# SECAM-TDA.net
KiCad netlist of a schematic drawn in EAGLE
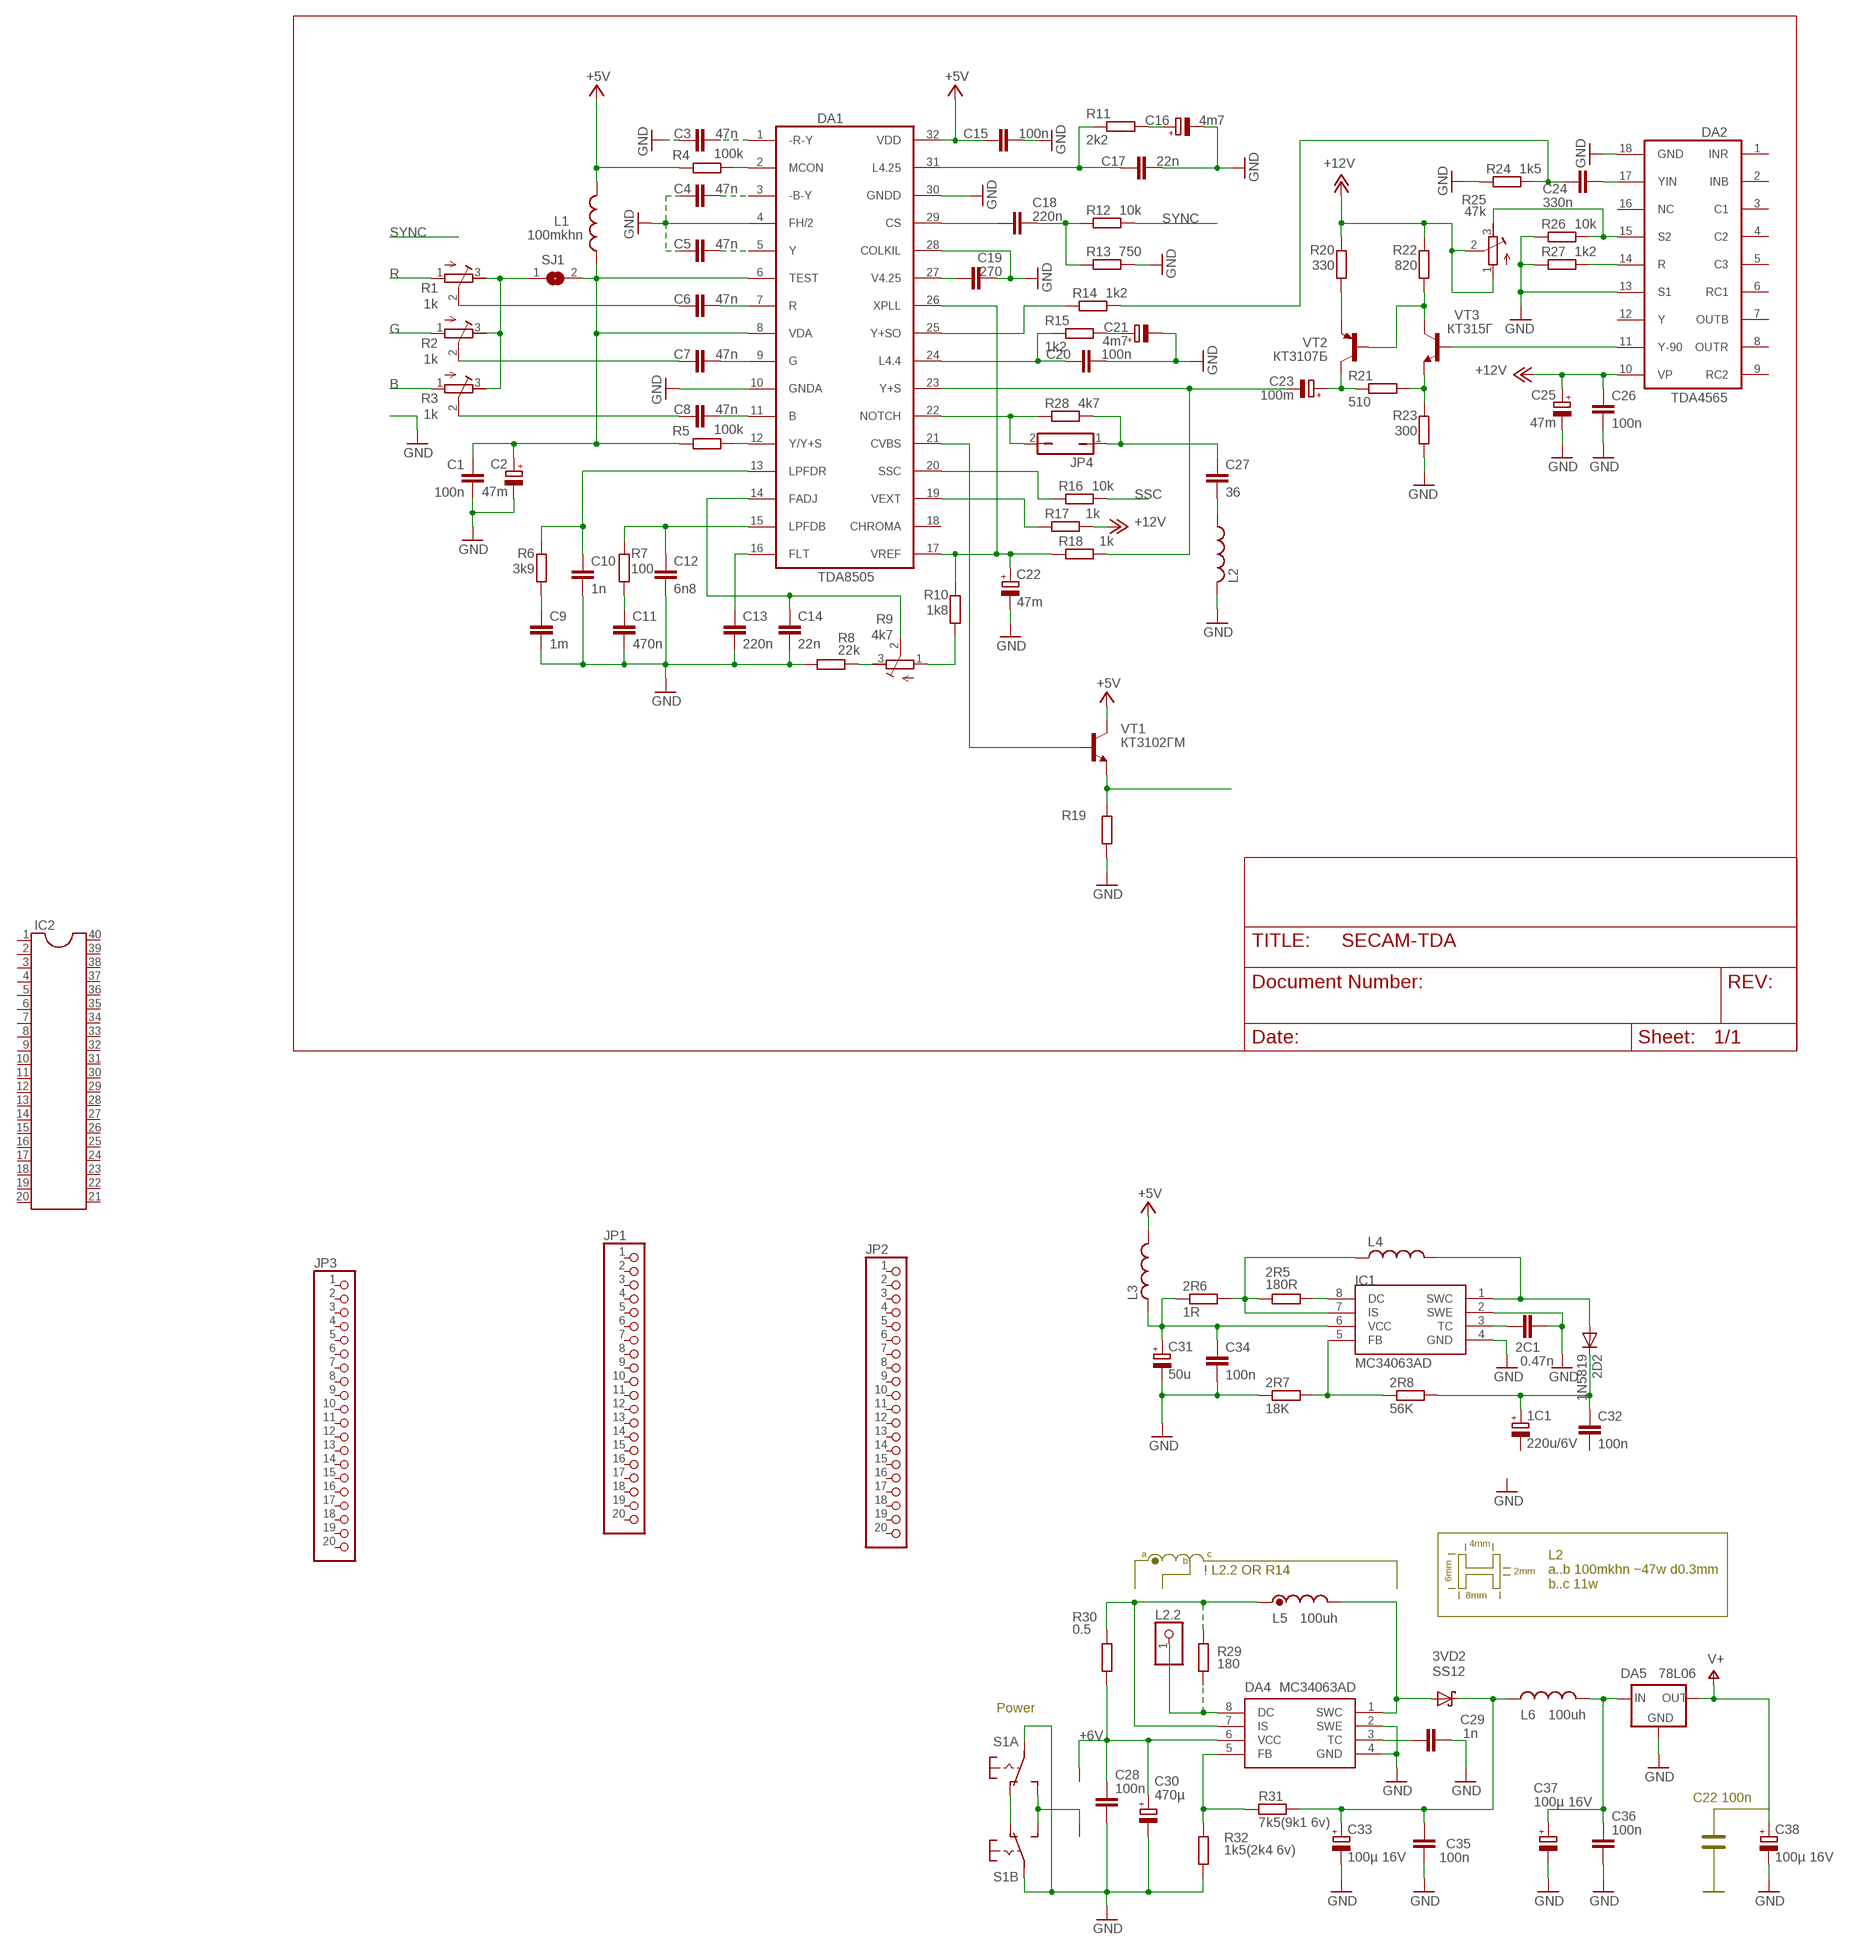
[diagram p0: schematic, sheet 1]

(export (version "E")
  (design (tool "Eeschema 10.0.6"))
  (components
    (comp (ref "1C1")
      (value "220u/6V")
      (footprint "eagle-import:E3,5-8")
      (libsource (lib "eagle-import") (part "resistor_CPOL-EUE3.5-8"))
    )
    (comp (ref "2C1")
      (value "0.47n")
      (footprint "eagle-import:C0805K")
      (libsource (lib "eagle-import") (part "resistor_C-EUC0805K"))
    )
    (comp (ref "2D2")
      (value "1N5819")
      (footprint "eagle-import:SMB")
      (libsource (lib "eagle-import") (part "DIODE-SMB"))
    )
    (comp (ref "2R5")
      (value "180R")
      (footprint "eagle-import:R0805")
      (libsource (lib "eagle-import") (part "resistor_R-EU_R0805"))
    )
    (comp (ref "2R6")
      (value "1R")
      (footprint "eagle-import:R0805")
      (libsource (lib "eagle-import") (part "resistor_R-EU_R0805"))
    )
    (comp (ref "2R7")
      (value "18K")
      (footprint "eagle-import:R0805")
      (libsource (lib "eagle-import") (part "resistor_R-EU_R0805"))
    )
    (comp (ref "2R8")
      (value "56K")
      (footprint "eagle-import:R0805")
      (libsource (lib "eagle-import") (part "resistor_R-EU_R0805"))
    )
    (comp (ref "3VD2")
      (value "SS12")
      (footprint "eagle-import:SMB")
      (libsource (lib "eagle-import") (part "SCHOTTKY-DIODESMD"))
    )
    (comp (ref "C1")
      (value "100n")
      (footprint "eagle-import:C0805")
      (libsource (lib "eagle-import") (part "rcl_C-EUC0805"))
    )
    (comp (ref "C2")
      (value "47m")
      (footprint "eagle-import:E2,5-5")
      (libsource (lib "eagle-import") (part "CPOL-EUE2.5-5"))
    )
    (comp (ref "C3")
      (value "47n")
      (footprint "eagle-import:C025-025X050")
      (libsource (lib "eagle-import") (part "rcl_C-EU025-025X050"))
    )
    (comp (ref "C4")
      (value "47n")
      (footprint "eagle-import:C025-025X050")
      (libsource (lib "eagle-import") (part "rcl_C-EU025-025X050"))
    )
    (comp (ref "C5")
      (value "47n")
      (footprint "eagle-import:C025-025X050")
      (libsource (lib "eagle-import") (part "rcl_C-EU025-025X050"))
    )
    (comp (ref "C6")
      (value "47n")
      (footprint "eagle-import:C025-025X050")
      (libsource (lib "eagle-import") (part "rcl_C-EU025-025X050"))
    )
    (comp (ref "C7")
      (value "47n")
      (footprint "eagle-import:C025-025X050")
      (libsource (lib "eagle-import") (part "rcl_C-EU025-025X050"))
    )
    (comp (ref "C8")
      (value "47n")
      (footprint "eagle-import:C025-025X050")
      (libsource (lib "eagle-import") (part "rcl_C-EU025-025X050"))
    )
    (comp (ref "C9")
      (value "1m")
      (footprint "eagle-import:C025-025X050")
      (libsource (lib "eagle-import") (part "rcl_C-EU025-025X050"))
    )
    (comp (ref "C10")
      (value "1n")
      (footprint "eagle-import:C025-025X050")
      (libsource (lib "eagle-import") (part "rcl_C-EU025-025X050"))
    )
    (comp (ref "C11")
      (value "470n")
      (footprint "eagle-import:C025-025X050")
      (libsource (lib "eagle-import") (part "rcl_C-EU025-025X050"))
    )
    (comp (ref "C12")
      (value "6n8")
      (footprint "eagle-import:C025-025X050")
      (libsource (lib "eagle-import") (part "rcl_C-EU025-025X050"))
    )
    (comp (ref "C13")
      (value "220n")
      (footprint "eagle-import:C025-025X050")
      (libsource (lib "eagle-import") (part "rcl_C-EU025-025X050"))
    )
    (comp (ref "C14")
      (value "22n")
      (footprint "eagle-import:C025-025X050")
      (libsource (lib "eagle-import") (part "rcl_C-EU025-025X050"))
    )
    (comp (ref "C15")
      (value "100n")
      (footprint "eagle-import:C0805")
      (libsource (lib "eagle-import") (part "rcl_C-EUC0805"))
    )
    (comp (ref "C16")
      (value "4m7")
      (footprint "eagle-import:E2,5-5")
      (libsource (lib "eagle-import") (part "CPOL-EUE2.5-5"))
    )
    (comp (ref "C17")
      (value "22n")
      (footprint "eagle-import:C025-025X050")
      (libsource (lib "eagle-import") (part "rcl_C-EU025-025X050"))
    )
    (comp (ref "C18")
      (value "220n")
      (footprint "eagle-import:C025-025X050")
      (libsource (lib "eagle-import") (part "rcl_C-EU025-025X050"))
    )
    (comp (ref "C19")
      (value "270")
      (footprint "eagle-import:C025-025X050")
      (libsource (lib "eagle-import") (part "rcl_C-EU025-025X050"))
    )
    (comp (ref "C20")
      (value "100n")
      (footprint "eagle-import:C0805")
      (libsource (lib "eagle-import") (part "rcl_C-EUC0805"))
    )
    (comp (ref "C21")
      (value "4m7")
      (footprint "eagle-import:E2,5-5")
      (libsource (lib "eagle-import") (part "CPOL-EUE2.5-5"))
    )
    (comp (ref "C22")
      (value "47m")
      (footprint "eagle-import:E2,5-5")
      (libsource (lib "eagle-import") (part "CPOL-EUE2.5-5"))
    )
    (comp (ref "C23")
      (value "100m")
      (footprint "eagle-import:E2,5-5")
      (libsource (lib "eagle-import") (part "CPOL-EUE2.5-5"))
    )
    (comp (ref "C24")
      (value "330n")
      (footprint "eagle-import:C025-025X050")
      (libsource (lib "eagle-import") (part "rcl_C-EU025-025X050"))
    )
    (comp (ref "C25")
      (value "47m")
      (footprint "eagle-import:E2,5-5")
      (libsource (lib "eagle-import") (part "CPOL-EUE2.5-5"))
    )
    (comp (ref "C26")
      (value "100n")
      (footprint "eagle-import:C0805")
      (libsource (lib "eagle-import") (part "rcl_C-EUC0805"))
    )
    (comp (ref "C27")
      (value "36")
      (footprint "eagle-import:C0805")
      (libsource (lib "eagle-import") (part "rcl_C-EUC0805"))
    )
    (comp (ref "C28")
      (value "100n")
      (footprint "eagle-import:C0805")
      (libsource (lib "eagle-import") (part "C-EUC0805"))
    )
    (comp (ref "C29")
      (value "1n")
      (footprint "eagle-import:C0805")
      (libsource (lib "eagle-import") (part "rcl_C-EUC0805"))
    )
    (comp (ref "C30")
      (value "470µ")
      (footprint "eagle-import:RCL_E2,5-7")
      (libsource (lib "eagle-import") (part "RCL_CPOL-EUE2.5-7"))
    )
    (comp (ref "C31")
      (value "50u")
      (footprint "eagle-import:E2,5-6")
      (libsource (lib "eagle-import") (part "resistor_CPOL-EUE2.5-6"))
    )
    (comp (ref "C32")
      (value "100n")
      (footprint "eagle-import:C0805K")
      (libsource (lib "eagle-import") (part "resistor_C-EUC0805K"))
    )
    (comp (ref "C33")
      (value "100µ 16V")
      (footprint "eagle-import:RCL_E2,5-5")
      (libsource (lib "eagle-import") (part "RCL_CPOL-EUE2.5-5"))
    )
    (comp (ref "C34")
      (value "100n")
      (footprint "eagle-import:C0805K")
      (libsource (lib "eagle-import") (part "resistor_C-EUC0805K"))
    )
    (comp (ref "C35")
      (value "100n")
      (footprint "eagle-import:C0805")
      (libsource (lib "eagle-import") (part "rcl_C-EUC0805"))
    )
    (comp (ref "C36")
      (value "100n")
      (footprint "eagle-import:C0805")
      (libsource (lib "eagle-import") (part "rcl_C-EUC0805"))
    )
    (comp (ref "C37")
      (value "100µ 16V")
      (footprint "eagle-import:RCL_E2,5-5")
      (libsource (lib "eagle-import") (part "RCL_CPOL-EUE2.5-5"))
    )
    (comp (ref "C38")
      (value "100µ 16V")
      (footprint "eagle-import:RCL_E2,5-5")
      (libsource (lib "eagle-import") (part "RCL_CPOL-EUE2.5-5"))
    )
    (comp (ref "DA1")
      (value "TDA8505")
      (footprint "eagle-import:PDIP32")
      (libsource (lib "eagle-import") (part "TDA8505"))
    )
    (comp (ref "DA2")
      (value "TDA4565")
      (footprint "eagle-import:DIL18")
      (libsource (lib "eagle-import") (part "TDA4565"))
    )
    (comp (ref "DA4")
      (value "MC34063AD")
      (footprint "eagle-import:SOIC8")
      (libsource (lib "eagle-import") (part "MC34063AD"))
    )
    (comp (ref "DA5")
      (value "78L06")
      (footprint "eagle-import:SOT89R")
      (libsource (lib "eagle-import") (part "78LXX_SOT89"))
    )
    (comp (ref "IC1")
      (value "MC34063AD")
      (footprint "eagle-import:SOIC8")
      (libsource (lib "eagle-import") (part "MC34063AD"))
    )
    (comp (ref "IC2")
      (value "DIL40")
      (footprint "eagle-import:DIL40")
      (libsource (lib "eagle-import") (part "DIL40"))
    )
    (comp (ref "JP1")
      (value "PINHD-1X20")
      (footprint "eagle-import:1X20")
      (libsource (lib "eagle-import") (part "PINHD-1X20"))
    )
    (comp (ref "JP2")
      (value "PINHD-1X20")
      (footprint "eagle-import:1X20")
      (libsource (lib "eagle-import") (part "PINHD-1X20"))
    )
    (comp (ref "JP3")
      (value "PINHD-1X20")
      (footprint "eagle-import:1X20")
      (libsource (lib "eagle-import") (part "PINHD-1X20"))
    )
    (comp (ref "JP4")
      (value "JP1Q")
      (footprint "eagle-import:JP1")
      (libsource (lib "eagle-import") (part "JP1Q"))
    )
    (comp (ref "L1")
      (value "100mkhn")
      (footprint "eagle-import:0207_10")
      (libsource (lib "eagle-import") (part "L-US0207/10"))
    )
    (comp (ref "L2")
      (value "L0204/5")
      (footprint "eagle-import:0204_5")
      (libsource (lib "eagle-import") (part "L0204/5"))
    )
    (comp (ref "L2.2")
      (value "PINHD-1X1")
      (footprint "eagle-import:1X01")
      (libsource (lib "eagle-import") (part "PINHD-1X1"))
    )
    (comp (ref "L3")
      (value "L0204/7")
      (footprint "eagle-import:0204_7")
      (libsource (lib "eagle-import") (part "L0204/7"))
    )
    (comp (ref "L4")
      (value "L0204/7")
      (footprint "eagle-import:0204_7")
      (libsource (lib "eagle-import") (part "L0204/7"))
    )
    (comp (ref "L5")
      (value "100uh")
      (footprint "eagle-import:0204_7")
      (libsource (lib "eagle-import") (part "L-US0204/7"))
    )
    (comp (ref "L6")
      (value "100uh")
      (footprint "eagle-import:0207_10")
      (libsource (lib "eagle-import") (part "L-US0207/10"))
    )
    (comp (ref "R1")
      (value "1k")
      (footprint "eagle-import:RTRIM3296W")
      (libsource (lib "eagle-import") (part "R-TRIMM3296W"))
    )
    (comp (ref "R2")
      (value "1k")
      (footprint "eagle-import:RTRIM3296W")
      (libsource (lib "eagle-import") (part "R-TRIMM3296W"))
    )
    (comp (ref "R3")
      (value "1k")
      (footprint "eagle-import:RTRIM3296W")
      (libsource (lib "eagle-import") (part "R-TRIMM3296W"))
    )
    (comp (ref "R4")
      (value "100k")
      (footprint "eagle-import:R0805")
      (libsource (lib "eagle-import") (part "R-EU_R0805"))
    )
    (comp (ref "R5")
      (value "100k")
      (footprint "eagle-import:0204_7")
      (libsource (lib "eagle-import") (part "R-EU_0204/7"))
    )
    (comp (ref "R6")
      (value "3k9")
      (footprint "eagle-import:R0805")
      (libsource (lib "eagle-import") (part "R-EU_R0805"))
    )
    (comp (ref "R7")
      (value "100")
      (footprint "eagle-import:0204_7")
      (libsource (lib "eagle-import") (part "R-EU_0204/7"))
    )
    (comp (ref "R8")
      (value "22k")
      (footprint "eagle-import:R0805")
      (libsource (lib "eagle-import") (part "R-EU_R0805"))
    )
    (comp (ref "R9")
      (value "4k7")
      (footprint "eagle-import:RTRIM3296W")
      (libsource (lib "eagle-import") (part "R-TRIMM3296W"))
    )
    (comp (ref "R10")
      (value "1k8")
      (footprint "eagle-import:R0805")
      (libsource (lib "eagle-import") (part "R-EU_R0805"))
    )
    (comp (ref "R11")
      (value "2k2")
      (footprint "eagle-import:R0805")
      (libsource (lib "eagle-import") (part "R-EU_R0805"))
    )
    (comp (ref "R12")
      (value "10k")
      (footprint "eagle-import:R0805")
      (libsource (lib "eagle-import") (part "R-EU_R0805"))
    )
    (comp (ref "R13")
      (value "750")
      (footprint "eagle-import:R0805")
      (libsource (lib "eagle-import") (part "R-EU_R0805"))
    )
    (comp (ref "R14")
      (value "1k2")
      (footprint "eagle-import:0207_10")
      (libsource (lib "eagle-import") (part "R-EU_0207/10"))
    )
    (comp (ref "R15")
      (value "1k2")
      (footprint "eagle-import:R0805")
      (libsource (lib "eagle-import") (part "R-EU_R0805"))
    )
    (comp (ref "R16")
      (value "10k")
      (footprint "eagle-import:R0805")
      (libsource (lib "eagle-import") (part "R-EU_R0805"))
    )
    (comp (ref "R17")
      (value "1k")
      (footprint "eagle-import:R0805")
      (libsource (lib "eagle-import") (part "R-EU_R0805"))
    )
    (comp (ref "R18")
      (value "1k")
      (footprint "eagle-import:R0805")
      (libsource (lib "eagle-import") (part "R-EU_R0805"))
    )
    (comp (ref "R19")
      (value "R-EU_R0805")
      (footprint "eagle-import:R0805")
      (libsource (lib "eagle-import") (part "R-EU_R0805"))
    )
    (comp (ref "R20")
      (value "330")
      (footprint "eagle-import:R0805")
      (libsource (lib "eagle-import") (part "R-EU_R0805"))
    )
    (comp (ref "R21")
      (value "510")
      (footprint "eagle-import:R0805")
      (libsource (lib "eagle-import") (part "R-EU_R0805"))
    )
    (comp (ref "R22")
      (value "820")
      (footprint "eagle-import:R0805")
      (libsource (lib "eagle-import") (part "R-EU_R0805"))
    )
    (comp (ref "R23")
      (value "300")
      (footprint "eagle-import:R0805")
      (libsource (lib "eagle-import") (part "R-EU_R0805"))
    )
    (comp (ref "R24")
      (value "1k5")
      (footprint "eagle-import:R0805")
      (libsource (lib "eagle-import") (part "R-EU_R0805"))
    )
    (comp (ref "R25")
      (value "47k")
      (footprint "eagle-import:RTRIM3296W")
      (libsource (lib "eagle-import") (part "R-TRIMM3296W"))
    )
    (comp (ref "R26")
      (value "10k")
      (footprint "eagle-import:R0805")
      (libsource (lib "eagle-import") (part "R-EU_R0805"))
    )
    (comp (ref "R27")
      (value "1k2")
      (footprint "eagle-import:R0805")
      (libsource (lib "eagle-import") (part "R-EU_R0805"))
    )
    (comp (ref "R28")
      (value "4k7")
      (footprint "eagle-import:R0805")
      (libsource (lib "eagle-import") (part "R-EU_R0805"))
    )
    (comp (ref "R29")
      (value "180")
      (footprint "eagle-import:M0805")
      (libsource (lib "eagle-import") (part "R-EU_M0805"))
    )
    (comp (ref "R30")
      (value "0.5")
      (footprint "eagle-import:M1206")
      (libsource (lib "eagle-import") (part "R-EU_M1206"))
    )
    (comp (ref "R31")
      (value "7k5(9k1 6v)")
      (footprint "eagle-import:M0805")
      (libsource (lib "eagle-import") (part "R-EU_M0805"))
    )
    (comp (ref "R32")
      (value "1k5(2k4 6v)")
      (footprint "eagle-import:M0805")
      (libsource (lib "eagle-import") (part "R-EU_M0805"))
    )
    (comp (ref "S1")
      (value "SWITCH9X4")
      (footprint "eagle-import:SWITCH9X4")
      (libsource (lib "eagle-import") (part "SWITCH9X4"))
    )
    (comp (ref "SJ1") (value "SJ") (footprint "eagle-import:SJ") (libsource (lib "eagle-import") (part "SJ")))
    (comp (ref "U$5") (value "B-") (footprint "eagle-import:B-") (libsource (lib "eagle-import") (part "B-")))
    (comp (ref "U$6") (value "B+") (footprint "eagle-import:B+") (libsource (lib "eagle-import") (part "B+")))
    (comp (ref "VT1")
      (value "КТ3102ГМ")
      (footprint "eagle-import:TO92-EBC")
      (libsource (lib "eagle-import") (part "-NPN-TO92-EBC"))
    )
    (comp (ref "VT2")
      (value "КТ3107Б")
      (footprint "eagle-import:TO92-BCE")
      (libsource (lib "eagle-import") (part "BC369"))
    )
    (comp (ref "VT3")
      (value "КТ315Г")
      (footprint "eagle-import:TO92-ECB")
      (libsource (lib "eagle-import") (part "-NPN-TO92-ECB"))
    )
  )
  (nets
    (net (code "1") (name "+5V") (class "Default")
      (node (ref "C15") (pin "1") (pinfunction "1_1") (pintype "passive"))
      (node (ref "DA1") (pin "32") (pinfunction "VDD_32") (pintype "tri_state"))
      (node (ref "L1") (pin "2") (pinfunction "2_2") (pintype "passive"))
      (node (ref "L3") (pin "2") (pinfunction "2_2") (pintype "passive"))
      (node (ref "R4") (pin "1") (pinfunction "1_1") (pintype "passive"))
      (node (ref "VT1") (pin "C") (pinfunction "C_C") (pintype "passive"))
    )
    (net (code "2") (name "+12V") (class "Default")
      (node (ref "C25") (pin "+") (pinfunction "+_+") (pintype "passive"))
      (node (ref "C26") (pin "1") (pinfunction "1_1") (pintype "passive"))
      (node (ref "DA2") (pin "10") (pinfunction "VP_10") (pintype "tri_state"))
      (node (ref "R17") (pin "2") (pinfunction "2_2") (pintype "passive"))
      (node (ref "R20") (pin "2") (pinfunction "2_2") (pintype "passive"))
      (node (ref "R22") (pin "2") (pinfunction "2_2") (pintype "passive"))
      (node (ref "R25") (pin "1") (pinfunction "A_1") (pintype "passive"))
      (node (ref "R25") (pin "2") (pinfunction "S_2") (pintype "passive"))
    )
    (net (code "3") (name "/+6V") (class "Default")
      (node (ref "C28") (pin "1") (pinfunction "1_1") (pintype "passive"))
      (node (ref "C30") (pin "+") (pinfunction "+_+") (pintype "passive"))
      (node (ref "DA4") (pin "6") (pinfunction "VCC_6") (pintype "passive"))
      (node (ref "R30") (pin "1") (pinfunction "1_1") (pintype "passive"))
      (node (ref "U$6") (pin "P$1") (pinfunction "P$1_P$1") (pintype "bidirectional"))
    )
    (net (code "4") (name "/B") (class "Default")
      (node (ref "R3") (pin "1") (pinfunction "A_1") (pintype "passive"))
    )
    (net (code "5") (name "/G") (class "Default")
      (node (ref "R2") (pin "1") (pinfunction "A_1") (pintype "passive"))
    )
    (net (code "6") (name "/R") (class "Default")
      (node (ref "R1") (pin "1") (pinfunction "A_1") (pintype "passive"))
    )
    (net (code "7") (name "/SSC") (class "Default")
      (node (ref "R16") (pin "2") (pinfunction "2_2") (pintype "passive"))
    )
    (net (code "8") (name "/SYNC") (class "Default")
      (node (ref "R12") (pin "2") (pinfunction "2_2") (pintype "passive"))
    )
    (net (code "9") (name "GND") (class "Default")
      (node (ref "2C1") (pin "2") (pinfunction "2_2") (pintype "passive"))
      (node (ref "2R7") (pin "1") (pinfunction "1_1") (pintype "passive"))
      (node (ref "C1") (pin "2") (pinfunction "2_2") (pintype "passive"))
      (node (ref "C10") (pin "2") (pinfunction "2_2") (pintype "passive"))
      (node (ref "C11") (pin "2") (pinfunction "2_2") (pintype "passive"))
      (node (ref "C12") (pin "2") (pinfunction "2_2") (pintype "passive"))
      (node (ref "C13") (pin "2") (pinfunction "2_2") (pintype "passive"))
      (node (ref "C14") (pin "2") (pinfunction "2_2") (pintype "passive"))
      (node (ref "C15") (pin "2") (pinfunction "2_2") (pintype "passive"))
      (node (ref "C16") (pin "-") (pinfunction "-_-") (pintype "passive"))
      (node (ref "C17") (pin "2") (pinfunction "2_2") (pintype "passive"))
      (node (ref "C19") (pin "2") (pinfunction "2_2") (pintype "passive"))
      (node (ref "C2") (pin "-") (pinfunction "-_-") (pintype "passive"))
      (node (ref "C20") (pin "2") (pinfunction "2_2") (pintype "passive"))
      (node (ref "C21") (pin "-") (pinfunction "-_-") (pintype "passive"))
      (node (ref "C22") (pin "-") (pinfunction "-_-") (pintype "passive"))
      (node (ref "C25") (pin "-") (pinfunction "-_-") (pintype "passive"))
      (node (ref "C26") (pin "2") (pinfunction "2_2") (pintype "passive"))
      (node (ref "C28") (pin "2") (pinfunction "2_2") (pintype "passive"))
      (node (ref "C29") (pin "2") (pinfunction "2_2") (pintype "passive"))
      (node (ref "C3") (pin "1") (pinfunction "1_1") (pintype "passive"))
      (node (ref "C30") (pin "-") (pinfunction "-_-") (pintype "passive"))
      (node (ref "C31") (pin "-") (pinfunction "-_-") (pintype "passive"))
      (node (ref "C33") (pin "-") (pinfunction "-_-") (pintype "passive"))
      (node (ref "C34") (pin "2") (pinfunction "2_2") (pintype "passive"))
      (node (ref "C35") (pin "1") (pinfunction "1_1") (pintype "passive"))
      (node (ref "C36") (pin "2") (pinfunction "2_2") (pintype "passive"))
      (node (ref "C37") (pin "-") (pinfunction "-_-") (pintype "passive"))
      (node (ref "C38") (pin "-") (pinfunction "-_-") (pintype "passive"))
      (node (ref "C4") (pin "1") (pinfunction "1_1") (pintype "passive"))
      (node (ref "C5") (pin "1") (pinfunction "1_1") (pintype "passive"))
      (node (ref "C9") (pin "2") (pinfunction "2_2") (pintype "passive"))
      (node (ref "DA1") (pin "10") (pinfunction "GNDA_10") (pintype "input"))
      (node (ref "DA1") (pin "28") (pinfunction "COLKIL_28") (pintype "tri_state"))
      (node (ref "DA1") (pin "30") (pinfunction "GNDD_30") (pintype "tri_state"))
      (node (ref "DA1") (pin "4") (pinfunction "FH/2_4") (pintype "input"))
      (node (ref "DA2") (pin "13") (pinfunction "S1_13") (pintype "tri_state"))
      (node (ref "DA2") (pin "18") (pinfunction "GND_18") (pintype "tri_state"))
      (node (ref "DA4") (pin "2") (pinfunction "SWE_2") (pintype "passive"))
      (node (ref "DA4") (pin "4") (pinfunction "GND_4") (pintype "passive"))
      (node (ref "DA5") (pin "3") (pinfunction "GND_3") (pintype "input"))
      (node (ref "DA5") (pin "4") (pinfunction "GND_4") (pintype "input"))
      (node (ref "IC1") (pin "2") (pinfunction "SWE_2") (pintype "passive"))
      (node (ref "IC1") (pin "4") (pinfunction "GND_4") (pintype "passive"))
      (node (ref "L2") (pin "1") (pinfunction "1_1") (pintype "passive"))
      (node (ref "R13") (pin "2") (pinfunction "2_2") (pintype "passive"))
      (node (ref "R19") (pin "1") (pinfunction "1_1") (pintype "passive"))
      (node (ref "R23") (pin "1") (pinfunction "1_1") (pintype "passive"))
      (node (ref "R24") (pin "1") (pinfunction "1_1") (pintype "passive"))
      (node (ref "R26") (pin "1") (pinfunction "1_1") (pintype "passive"))
      (node (ref "R27") (pin "1") (pinfunction "1_1") (pintype "passive"))
      (node (ref "R32") (pin "1") (pinfunction "1_1") (pintype "passive"))
      (node (ref "R8") (pin "1") (pinfunction "1_1") (pintype "passive"))
      (node (ref "S1") (pin "10") (pinfunction "P_10") (pintype "passive"))
      (node (ref "S1") (pin "20") (pinfunction "P_20") (pintype "passive"))
    )
    (net (code "10") (name "Net-(1C1-Pad+)") (class "Default")
      (node (ref "1C1") (pin "+") (pinfunction "+_+") (pintype "passive"))
      (node (ref "2D2") (pin "C") (pinfunction "C_C") (pintype "passive"))
      (node (ref "2R8") (pin "2") (pinfunction "2_2") (pintype "passive"))
      (node (ref "C32") (pin "1") (pinfunction "1_1") (pintype "passive"))
    )
    (net (code "11") (name "Net-(3VD2-PadC)") (class "Default")
      (node (ref "3VD2") (pin "C") (pinfunction "C_C") (pintype "passive"))
      (node (ref "C33") (pin "+") (pinfunction "+_+") (pintype "passive"))
      (node (ref "C35") (pin "2") (pinfunction "2_2") (pintype "passive"))
      (node (ref "L6") (pin "1") (pinfunction "1_1") (pintype "passive"))
      (node (ref "R31") (pin "2") (pinfunction "2_2") (pintype "passive"))
    )
    (net (code "12") (name "Net-(C9-Pad1)") (class "Default")
      (node (ref "C9") (pin "1") (pinfunction "1_1") (pintype "passive"))
      (node (ref "R6") (pin "1") (pinfunction "1_1") (pintype "passive"))
    )
    (net (code "13") (name "Net-(C11-Pad1)") (class "Default")
      (node (ref "C11") (pin "1") (pinfunction "1_1") (pintype "passive"))
      (node (ref "R7") (pin "1") (pinfunction "1_1") (pintype "passive"))
    )
    (net (code "14") (name "Net-(C16-Pad+)") (class "Default")
      (node (ref "C16") (pin "+") (pinfunction "+_+") (pintype "passive"))
      (node (ref "R11") (pin "2") (pinfunction "2_2") (pintype "passive"))
    )
    (net (code "15") (name "Net-(C18-Pad2)") (class "Default")
      (node (ref "C18") (pin "2") (pinfunction "2_2") (pintype "passive"))
      (node (ref "R12") (pin "1") (pinfunction "1_1") (pintype "passive"))
      (node (ref "R13") (pin "1") (pinfunction "1_1") (pintype "passive"))
    )
    (net (code "16") (name "Net-(C21-Pad+)") (class "Default")
      (node (ref "C21") (pin "+") (pinfunction "+_+") (pintype "passive"))
      (node (ref "R15") (pin "2") (pinfunction "2_2") (pintype "passive"))
    )
    (net (code "17") (name "Net-(C23-Pad+)") (class "Default")
      (node (ref "C23") (pin "+") (pinfunction "+_+") (pintype "passive"))
      (node (ref "R21") (pin "1") (pinfunction "1_1") (pintype "passive"))
      (node (ref "VT2") (pin "C") (pinfunction "C_C") (pintype "passive"))
    )
    (net (code "18") (name "Net-(C24-Pad1)") (class "Default")
      (node (ref "C24") (pin "1") (pinfunction "1_1") (pintype "passive"))
      (node (ref "R14") (pin "2") (pinfunction "2_2") (pintype "passive"))
      (node (ref "R24") (pin "2") (pinfunction "2_2") (pintype "passive"))
    )
    (net (code "19") (name "Net-(C27-Pad1)") (class "Default")
      (node (ref "C27") (pin "1") (pinfunction "1_1") (pintype "passive"))
      (node (ref "JP4") (pin "1") (pinfunction "1_1") (pintype "passive"))
      (node (ref "R28") (pin "2") (pinfunction "2_2") (pintype "passive"))
    )
    (net (code "20") (name "Net-(C27-Pad2)") (class "Default")
      (node (ref "C27") (pin "2") (pinfunction "2_2") (pintype "passive"))
      (node (ref "L2") (pin "2") (pinfunction "2_2") (pintype "passive"))
    )
    (net (code "21") (name "Net-(DA1--B-Y)") (class "Default")
      (node (ref "C4") (pin "2") (pinfunction "2_2") (pintype "passive"))
      (node (ref "DA1") (pin "3") (pinfunction "-B-Y_3") (pintype "input"))
    )
    (net (code "22") (name "Net-(DA1--R-Y)") (class "Default")
      (node (ref "C3") (pin "2") (pinfunction "2_2") (pintype "passive"))
      (node (ref "DA1") (pin "1") (pinfunction "-R-Y_1") (pintype "input"))
    )
    (net (code "23") (name "Net-(DA1-B)") (class "Default")
      (node (ref "C8") (pin "2") (pinfunction "2_2") (pintype "passive"))
      (node (ref "DA1") (pin "11") (pinfunction "B_11") (pintype "input"))
    )
    (net (code "24") (name "Net-(DA1-CS)") (class "Default")
      (node (ref "C18") (pin "1") (pinfunction "1_1") (pintype "passive"))
      (node (ref "DA1") (pin "29") (pinfunction "CS_29") (pintype "tri_state"))
    )
    (net (code "25") (name "Net-(DA1-CVBS)") (class "Default")
      (node (ref "DA1") (pin "21") (pinfunction "CVBS_21") (pintype "tri_state"))
      (node (ref "VT1") (pin "B") (pinfunction "B_B") (pintype "passive"))
    )
    (net (code "26") (name "Net-(DA1-FADJ)") (class "Default")
      (node (ref "C14") (pin "1") (pinfunction "1_1") (pintype "passive"))
      (node (ref "DA1") (pin "14") (pinfunction "FADJ_14") (pintype "input"))
      (node (ref "R9") (pin "2") (pinfunction "S_2") (pintype "passive"))
    )
    (net (code "27") (name "Net-(DA1-FLT)") (class "Default")
      (node (ref "C13") (pin "1") (pinfunction "1_1") (pintype "passive"))
      (node (ref "DA1") (pin "16") (pinfunction "FLT_16") (pintype "input"))
    )
    (net (code "28") (name "Net-(DA1-G)") (class "Default")
      (node (ref "C7") (pin "2") (pinfunction "2_2") (pintype "passive"))
      (node (ref "DA1") (pin "9") (pinfunction "G_9") (pintype "input"))
    )
    (net (code "29") (name "Net-(DA1-L4.4)") (class "Default")
      (node (ref "C20") (pin "1") (pinfunction "1_1") (pintype "passive"))
      (node (ref "DA1") (pin "24") (pinfunction "L4.4_24") (pintype "tri_state"))
      (node (ref "R15") (pin "1") (pinfunction "1_1") (pintype "passive"))
    )
    (net (code "30") (name "Net-(DA1-L4.25)") (class "Default")
      (node (ref "C17") (pin "1") (pinfunction "1_1") (pintype "passive"))
      (node (ref "DA1") (pin "31") (pinfunction "L4.25_31") (pintype "tri_state"))
      (node (ref "R11") (pin "1") (pinfunction "1_1") (pintype "passive"))
    )
    (net (code "31") (name "Net-(DA1-LPFDB)") (class "Default")
      (node (ref "C12") (pin "1") (pinfunction "1_1") (pintype "passive"))
      (node (ref "DA1") (pin "15") (pinfunction "LPFDB_15") (pintype "input"))
      (node (ref "R7") (pin "2") (pinfunction "2_2") (pintype "passive"))
    )
    (net (code "32") (name "Net-(DA1-LPFDR)") (class "Default")
      (node (ref "C10") (pin "1") (pinfunction "1_1") (pintype "passive"))
      (node (ref "DA1") (pin "13") (pinfunction "LPFDR_13") (pintype "input"))
      (node (ref "R6") (pin "2") (pinfunction "2_2") (pintype "passive"))
    )
    (net (code "33") (name "Net-(DA1-MCON)") (class "Default")
      (node (ref "DA1") (pin "2") (pinfunction "MCON_2") (pintype "input"))
      (node (ref "R4") (pin "2") (pinfunction "2_2") (pintype "passive"))
    )
    (net (code "34") (name "Net-(DA1-NOTCH)") (class "Default")
      (node (ref "DA1") (pin "22") (pinfunction "NOTCH_22") (pintype "tri_state"))
      (node (ref "JP4") (pin "2") (pinfunction "2_2") (pintype "passive"))
      (node (ref "R28") (pin "1") (pinfunction "1_1") (pintype "passive"))
    )
    (net (code "35") (name "Net-(DA1-R)") (class "Default")
      (node (ref "C6") (pin "2") (pinfunction "2_2") (pintype "passive"))
      (node (ref "DA1") (pin "7") (pinfunction "R_7") (pintype "input"))
    )
    (net (code "36") (name "Net-(DA1-SSC)") (class "Default")
      (node (ref "DA1") (pin "20") (pinfunction "SSC_20") (pintype "tri_state"))
      (node (ref "R16") (pin "1") (pinfunction "1_1") (pintype "passive"))
    )
    (net (code "37") (name "Net-(DA1-TEST)") (class "Default")
      (node (ref "C1") (pin "1") (pinfunction "1_1") (pintype "passive"))
      (node (ref "C2") (pin "+") (pinfunction "+_+") (pintype "passive"))
      (node (ref "DA1") (pin "6") (pinfunction "TEST_6") (pintype "input"))
      (node (ref "DA1") (pin "8") (pinfunction "VDA_8") (pintype "input"))
      (node (ref "L1") (pin "1") (pinfunction "1_1") (pintype "passive"))
      (node (ref "R5") (pin "1") (pinfunction "1_1") (pintype "passive"))
      (node (ref "SJ1") (pin "2") (pinfunction "2_2") (pintype "passive"))
    )
    (net (code "38") (name "Net-(DA1-V4.25)") (class "Default")
      (node (ref "C19") (pin "1") (pinfunction "1_1") (pintype "passive"))
      (node (ref "DA1") (pin "27") (pinfunction "V4.25_27") (pintype "tri_state"))
    )
    (net (code "39") (name "Net-(DA1-VEXT)") (class "Default")
      (node (ref "DA1") (pin "19") (pinfunction "VEXT_19") (pintype "tri_state"))
      (node (ref "R17") (pin "1") (pinfunction "1_1") (pintype "passive"))
    )
    (net (code "40") (name "Net-(DA1-VREF)") (class "Default")
      (node (ref "C22") (pin "+") (pinfunction "+_+") (pintype "passive"))
      (node (ref "DA1") (pin "17") (pinfunction "VREF_17") (pintype "tri_state"))
      (node (ref "DA1") (pin "26") (pinfunction "XPLL_26") (pintype "tri_state"))
      (node (ref "R10") (pin "2") (pinfunction "2_2") (pintype "passive"))
      (node (ref "R18") (pin "1") (pinfunction "1_1") (pintype "passive"))
    )
    (net (code "41") (name "Net-(DA1-Y)") (class "Default")
      (node (ref "C5") (pin "2") (pinfunction "2_2") (pintype "passive"))
      (node (ref "DA1") (pin "5") (pinfunction "Y_5") (pintype "input"))
    )
    (net (code "42") (name "Net-(DA1-Y+S)") (class "Default")
      (node (ref "C23") (pin "-") (pinfunction "-_-") (pintype "passive"))
      (node (ref "DA1") (pin "23") (pinfunction "Y+S_23") (pintype "tri_state"))
      (node (ref "R18") (pin "2") (pinfunction "2_2") (pintype "passive"))
    )
    (net (code "43") (name "Net-(DA1-Y+SO)") (class "Default")
      (node (ref "DA1") (pin "25") (pinfunction "Y+SO_25") (pintype "tri_state"))
      (node (ref "R14") (pin "1") (pinfunction "1_1") (pintype "passive"))
    )
    (net (code "44") (name "Net-(DA1-Y{slash}Y+S)") (class "Default")
      (node (ref "DA1") (pin "12") (pinfunction "Y/Y+S_12") (pintype "input"))
      (node (ref "R5") (pin "2") (pinfunction "2_2") (pintype "passive"))
    )
    (net (code "45") (name "Net-(DA2-R)") (class "Default")
      (node (ref "DA2") (pin "14") (pinfunction "R_14") (pintype "tri_state"))
      (node (ref "R27") (pin "2") (pinfunction "2_2") (pintype "passive"))
    )
    (net (code "46") (name "Net-(DA2-S2)") (class "Default")
      (node (ref "DA2") (pin "15") (pinfunction "S2_15") (pintype "tri_state"))
      (node (ref "R25") (pin "3") (pinfunction "E_3") (pintype "passive"))
      (node (ref "R26") (pin "2") (pinfunction "2_2") (pintype "passive"))
    )
    (net (code "47") (name "Net-(DA2-Y-90)") (class "Default")
      (node (ref "DA2") (pin "11") (pinfunction "Y-90_11") (pintype "tri_state"))
      (node (ref "VT3") (pin "B") (pinfunction "B_B") (pintype "passive"))
    )
    (net (code "48") (name "Net-(DA2-YIN)") (class "Default")
      (node (ref "C24") (pin "2") (pinfunction "2_2") (pintype "passive"))
      (node (ref "DA2") (pin "17") (pinfunction "YIN_17") (pintype "tri_state"))
    )
    (net (code "49") (name "Net-(DA4-DC)") (class "Default")
      (node (ref "DA4") (pin "8") (pinfunction "DC_8") (pintype "passive"))
      (node (ref "L2.2") (pin "1") (pinfunction "1_1") (pintype "passive"))
      (node (ref "R29") (pin "1") (pinfunction "1_1") (pintype "passive"))
    )
    (net (code "50") (name "Net-(DA4-FB)") (class "Default")
      (node (ref "DA4") (pin "5") (pinfunction "FB_5") (pintype "passive"))
      (node (ref "R31") (pin "1") (pinfunction "1_1") (pintype "passive"))
      (node (ref "R32") (pin "2") (pinfunction "2_2") (pintype "passive"))
    )
    (net (code "51") (name "Net-(DA4-IS)") (class "Default")
      (node (ref "DA4") (pin "7") (pinfunction "IS_7") (pintype "passive"))
      (node (ref "L5") (pin "1") (pinfunction "1_1") (pintype "passive"))
      (node (ref "R29") (pin "2") (pinfunction "2_2") (pintype "passive"))
      (node (ref "R30") (pin "2") (pinfunction "2_2") (pintype "passive"))
    )
    (net (code "52") (name "Net-(DA4-SWC)") (class "Default")
      (node (ref "3VD2") (pin "A") (pinfunction "A_A") (pintype "passive"))
      (node (ref "DA4") (pin "1") (pinfunction "SWC_1") (pintype "passive"))
      (node (ref "L5") (pin "2") (pinfunction "2_2") (pintype "passive"))
    )
    (net (code "53") (name "Net-(DA4-TC)") (class "Default")
      (node (ref "C29") (pin "1") (pinfunction "1_1") (pintype "passive"))
      (node (ref "DA4") (pin "3") (pinfunction "TC_3") (pintype "passive"))
    )
    (net (code "54") (name "Net-(DA5-IN)") (class "Default")
      (node (ref "C36") (pin "1") (pinfunction "1_1") (pintype "passive"))
      (node (ref "C37") (pin "+") (pinfunction "+_+") (pintype "passive"))
      (node (ref "DA5") (pin "1") (pinfunction "IN_1") (pintype "input"))
      (node (ref "L6") (pin "2") (pinfunction "2_2") (pintype "passive"))
    )
    (net (code "55") (name "Net-(IC1-DC)") (class "Default")
      (node (ref "2R5") (pin "2") (pinfunction "2_2") (pintype "passive"))
      (node (ref "IC1") (pin "8") (pinfunction "DC_8") (pintype "passive"))
    )
    (net (code "56") (name "Net-(IC1-FB)") (class "Default")
      (node (ref "2R7") (pin "2") (pinfunction "2_2") (pintype "passive"))
      (node (ref "2R8") (pin "1") (pinfunction "1_1") (pintype "passive"))
      (node (ref "IC1") (pin "5") (pinfunction "FB_5") (pintype "passive"))
    )
    (net (code "57") (name "Net-(IC1-IS)") (class "Default")
      (node (ref "2R5") (pin "1") (pinfunction "1_1") (pintype "passive"))
      (node (ref "2R6") (pin "2") (pinfunction "2_2") (pintype "passive"))
      (node (ref "IC1") (pin "7") (pinfunction "IS_7") (pintype "passive"))
      (node (ref "L4") (pin "1") (pinfunction "1_1") (pintype "passive"))
    )
    (net (code "58") (name "Net-(IC1-SWC)") (class "Default")
      (node (ref "2D2") (pin "A") (pinfunction "A_A") (pintype "passive"))
      (node (ref "IC1") (pin "1") (pinfunction "SWC_1") (pintype "passive"))
      (node (ref "L4") (pin "2") (pinfunction "2_2") (pintype "passive"))
    )
    (net (code "59") (name "Net-(IC1-TC)") (class "Default")
      (node (ref "2C1") (pin "1") (pinfunction "1_1") (pintype "passive"))
      (node (ref "IC1") (pin "3") (pinfunction "TC_3") (pintype "passive"))
    )
    (net (code "60") (name "Net-(IC1-VCC)") (class "Default")
      (node (ref "2R6") (pin "1") (pinfunction "1_1") (pintype "passive"))
      (node (ref "C31") (pin "+") (pinfunction "+_+") (pintype "passive"))
      (node (ref "C34") (pin "1") (pinfunction "1_1") (pintype "passive"))
      (node (ref "IC1") (pin "6") (pinfunction "VCC_6") (pintype "passive"))
      (node (ref "L3") (pin "1") (pinfunction "1_1") (pintype "passive"))
    )
    (net (code "61") (name "Net-(R1-E)") (class "Default")
      (node (ref "R1") (pin "3") (pinfunction "E_3") (pintype "passive"))
      (node (ref "R2") (pin "3") (pinfunction "E_3") (pintype "passive"))
      (node (ref "R3") (pin "3") (pinfunction "E_3") (pintype "passive"))
      (node (ref "SJ1") (pin "1") (pinfunction "1_1") (pintype "passive"))
    )
    (net (code "62") (name "Net-(R1-S)") (class "Default")
      (node (ref "C6") (pin "1") (pinfunction "1_1") (pintype "passive"))
      (node (ref "R1") (pin "2") (pinfunction "S_2") (pintype "passive"))
    )
    (net (code "63") (name "Net-(R2-S)") (class "Default")
      (node (ref "C7") (pin "1") (pinfunction "1_1") (pintype "passive"))
      (node (ref "R2") (pin "2") (pinfunction "S_2") (pintype "passive"))
    )
    (net (code "64") (name "Net-(R3-S)") (class "Default")
      (node (ref "C8") (pin "1") (pinfunction "1_1") (pintype "passive"))
      (node (ref "R3") (pin "2") (pinfunction "S_2") (pintype "passive"))
    )
    (net (code "65") (name "Net-(R9-A)") (class "Default")
      (node (ref "R10") (pin "1") (pinfunction "1_1") (pintype "passive"))
      (node (ref "R9") (pin "1") (pinfunction "A_1") (pintype "passive"))
    )
    (net (code "66") (name "Net-(R9-E)") (class "Default")
      (node (ref "R8") (pin "2") (pinfunction "2_2") (pintype "passive"))
      (node (ref "R9") (pin "3") (pinfunction "E_3") (pintype "passive"))
    )
    (net (code "67") (name "Net-(R19-Pad2)") (class "Default")
      (node (ref "R19") (pin "2") (pinfunction "2_2") (pintype "passive"))
      (node (ref "VT1") (pin "E") (pinfunction "E_E") (pintype "passive"))
    )
    (net (code "68") (name "Net-(R20-Pad1)") (class "Default")
      (node (ref "R20") (pin "1") (pinfunction "1_1") (pintype "passive"))
      (node (ref "VT2") (pin "E") (pinfunction "E_E") (pintype "passive"))
    )
    (net (code "69") (name "Net-(R21-Pad2)") (class "Default")
      (node (ref "R21") (pin "2") (pinfunction "2_2") (pintype "passive"))
      (node (ref "R23") (pin "2") (pinfunction "2_2") (pintype "passive"))
      (node (ref "VT3") (pin "E") (pinfunction "E_E") (pintype "passive"))
    )
    (net (code "70") (name "Net-(R22-Pad1)") (class "Default")
      (node (ref "R22") (pin "1") (pinfunction "1_1") (pintype "passive"))
      (node (ref "VT2") (pin "B") (pinfunction "B_B") (pintype "passive"))
      (node (ref "VT3") (pin "C") (pinfunction "C_C") (pintype "passive"))
    )
    (net (code "71") (name "Net-(S1A-O)") (class "Default")
      (node (ref "S1") (pin "11") (pinfunction "O_11") (pintype "passive"))
      (node (ref "S1") (pin "21") (pinfunction "O_21") (pintype "passive"))
    )
    (net (code "72") (name "Net-(S1A-S)") (class "Default")
      (node (ref "S1") (pin "12") (pinfunction "S_12") (pintype "passive"))
      (node (ref "S1") (pin "22") (pinfunction "S_22") (pintype "passive"))
      (node (ref "U$5") (pin "P$1") (pinfunction "P$1_P$1") (pintype "bidirectional"))
    )
    (net (code "73") (name "V+") (class "Default")
      (node (ref "C38") (pin "+") (pinfunction "+_+") (pintype "passive"))
      (node (ref "DA5") (pin "2") (pinfunction "OUT_2") (pintype "passive"))
    )
    (net (code "74") (name "unconnected-(1C1-Pad-)") (class "Default")
      (node (ref "1C1") (pin "-") (pinfunction "-_-") (pintype "passive"))
    )
    (net (code "75") (name "unconnected-(C32-Pad2)") (class "Default")
      (node (ref "C32") (pin "2") (pinfunction "2_2") (pintype "passive"))
    )
    (net (code "76") (name "unconnected-(DA1-CHROMA-Pad18)") (class "Default")
      (node (ref "DA1") (pin "18") (pinfunction "CHROMA_18") (pintype "tri_state"))
    )
    (net (code "77") (name "unconnected-(DA2-C1-Pad3)") (class "Default")
      (node (ref "DA2") (pin "3") (pinfunction "C1_3") (pintype "input"))
    )
    (net (code "78") (name "unconnected-(DA2-C2-Pad4)") (class "Default")
      (node (ref "DA2") (pin "4") (pinfunction "C2_4") (pintype "input"))
    )
    (net (code "79") (name "unconnected-(DA2-C3-Pad5)") (class "Default")
      (node (ref "DA2") (pin "5") (pinfunction "C3_5") (pintype "input"))
    )
    (net (code "80") (name "unconnected-(DA2-INB-Pad2)") (class "Default")
      (node (ref "DA2") (pin "2") (pinfunction "INB_2") (pintype "input"))
    )
    (net (code "81") (name "unconnected-(DA2-INR-Pad1)") (class "Default")
      (node (ref "DA2") (pin "1") (pinfunction "INR_1") (pintype "input"))
    )
    (net (code "82") (name "unconnected-(DA2-NC-Pad16)") (class "Default")
      (node (ref "DA2") (pin "16") (pinfunction "NC_16") (pintype "tri_state"))
    )
    (net (code "83") (name "unconnected-(DA2-OUTB-Pad7)") (class "Default")
      (node (ref "DA2") (pin "7") (pinfunction "OUTB_7") (pintype "input"))
    )
    (net (code "84") (name "unconnected-(DA2-OUTR-Pad8)") (class "Default")
      (node (ref "DA2") (pin "8") (pinfunction "OUTR_8") (pintype "input"))
    )
    (net (code "85") (name "unconnected-(DA2-RC1-Pad6)") (class "Default")
      (node (ref "DA2") (pin "6") (pinfunction "RC1_6") (pintype "input"))
    )
    (net (code "86") (name "unconnected-(DA2-RC2-Pad9)") (class "Default")
      (node (ref "DA2") (pin "9") (pinfunction "RC2_9") (pintype "input"))
    )
    (net (code "87") (name "unconnected-(DA2-Y-Pad12)") (class "Default")
      (node (ref "DA2") (pin "12") (pinfunction "Y_12") (pintype "tri_state"))
    )
    (net (code "88") (name "unconnected-(IC2-Pad1)") (class "Default")
      (node (ref "IC2") (pin "1") (pinfunction "1_1") (pintype "passive"))
    )
    (net (code "89") (name "unconnected-(IC2-Pad2)") (class "Default")
      (node (ref "IC2") (pin "2") (pinfunction "2_2") (pintype "passive"))
    )
    (net (code "90") (name "unconnected-(IC2-Pad3)") (class "Default")
      (node (ref "IC2") (pin "3") (pinfunction "3_3") (pintype "passive"))
    )
    (net (code "91") (name "unconnected-(IC2-Pad4)") (class "Default")
      (node (ref "IC2") (pin "4") (pinfunction "4_4") (pintype "passive"))
    )
    (net (code "92") (name "unconnected-(IC2-Pad5)") (class "Default")
      (node (ref "IC2") (pin "5") (pinfunction "5_5") (pintype "passive"))
    )
    (net (code "93") (name "unconnected-(IC2-Pad6)") (class "Default")
      (node (ref "IC2") (pin "6") (pinfunction "6_6") (pintype "passive"))
    )
    (net (code "94") (name "unconnected-(IC2-Pad7)") (class "Default")
      (node (ref "IC2") (pin "7") (pinfunction "7_7") (pintype "passive"))
    )
    (net (code "95") (name "unconnected-(IC2-Pad8)") (class "Default")
      (node (ref "IC2") (pin "8") (pinfunction "8_8") (pintype "passive"))
    )
    (net (code "96") (name "unconnected-(IC2-Pad9)") (class "Default")
      (node (ref "IC2") (pin "9") (pinfunction "9_9") (pintype "passive"))
    )
    (net (code "97") (name "unconnected-(IC2-Pad10)") (class "Default")
      (node (ref "IC2") (pin "10") (pinfunction "10_10") (pintype "passive"))
    )
    (net (code "98") (name "unconnected-(IC2-Pad11)") (class "Default")
      (node (ref "IC2") (pin "11") (pinfunction "11_11") (pintype "passive"))
    )
    (net (code "99") (name "unconnected-(IC2-Pad12)") (class "Default")
      (node (ref "IC2") (pin "12") (pinfunction "12_12") (pintype "passive"))
    )
    (net (code "100") (name "unconnected-(IC2-Pad13)") (class "Default")
      (node (ref "IC2") (pin "13") (pinfunction "13_13") (pintype "passive"))
    )
    (net (code "101") (name "unconnected-(IC2-Pad14)") (class "Default")
      (node (ref "IC2") (pin "14") (pinfunction "14_14") (pintype "passive"))
    )
    (net (code "102") (name "unconnected-(IC2-Pad15)") (class "Default")
      (node (ref "IC2") (pin "15") (pinfunction "15_15") (pintype "passive"))
    )
    (net (code "103") (name "unconnected-(IC2-Pad16)") (class "Default")
      (node (ref "IC2") (pin "16") (pinfunction "16_16") (pintype "passive"))
    )
    (net (code "104") (name "unconnected-(IC2-Pad17)") (class "Default")
      (node (ref "IC2") (pin "17") (pinfunction "17_17") (pintype "passive"))
    )
    (net (code "105") (name "unconnected-(IC2-Pad18)") (class "Default")
      (node (ref "IC2") (pin "18") (pinfunction "18_18") (pintype "passive"))
    )
    (net (code "106") (name "unconnected-(IC2-Pad19)") (class "Default")
      (node (ref "IC2") (pin "19") (pinfunction "19_19") (pintype "passive"))
    )
    (net (code "107") (name "unconnected-(IC2-Pad20)") (class "Default")
      (node (ref "IC2") (pin "20") (pinfunction "20_20") (pintype "passive"))
    )
    (net (code "108") (name "unconnected-(IC2-Pad21)") (class "Default")
      (node (ref "IC2") (pin "21") (pinfunction "21_21") (pintype "passive"))
    )
    (net (code "109") (name "unconnected-(IC2-Pad22)") (class "Default")
      (node (ref "IC2") (pin "22") (pinfunction "22_22") (pintype "passive"))
    )
    (net (code "110") (name "unconnected-(IC2-Pad23)") (class "Default")
      (node (ref "IC2") (pin "23") (pinfunction "23_23") (pintype "passive"))
    )
    (net (code "111") (name "unconnected-(IC2-Pad24)") (class "Default")
      (node (ref "IC2") (pin "24") (pinfunction "24_24") (pintype "passive"))
    )
    (net (code "112") (name "unconnected-(IC2-Pad25)") (class "Default")
      (node (ref "IC2") (pin "25") (pinfunction "25_25") (pintype "passive"))
    )
    (net (code "113") (name "unconnected-(IC2-Pad26)") (class "Default")
      (node (ref "IC2") (pin "26") (pinfunction "26_26") (pintype "passive"))
    )
    (net (code "114") (name "unconnected-(IC2-Pad27)") (class "Default")
      (node (ref "IC2") (pin "27") (pinfunction "27_27") (pintype "passive"))
    )
    (net (code "115") (name "unconnected-(IC2-Pad28)") (class "Default")
      (node (ref "IC2") (pin "28") (pinfunction "28_28") (pintype "passive"))
    )
    (net (code "116") (name "unconnected-(IC2-Pad29)") (class "Default")
      (node (ref "IC2") (pin "29") (pinfunction "29_29") (pintype "passive"))
    )
    (net (code "117") (name "unconnected-(IC2-Pad30)") (class "Default")
      (node (ref "IC2") (pin "30") (pinfunction "30_30") (pintype "passive"))
    )
    (net (code "118") (name "unconnected-(IC2-Pad31)") (class "Default")
      (node (ref "IC2") (pin "31") (pinfunction "31_31") (pintype "passive"))
    )
    (net (code "119") (name "unconnected-(IC2-Pad32)") (class "Default")
      (node (ref "IC2") (pin "32") (pinfunction "32_32") (pintype "passive"))
    )
    (net (code "120") (name "unconnected-(IC2-Pad33)") (class "Default")
      (node (ref "IC2") (pin "33") (pinfunction "33_33") (pintype "passive"))
    )
    (net (code "121") (name "unconnected-(IC2-Pad34)") (class "Default")
      (node (ref "IC2") (pin "34") (pinfunction "34_34") (pintype "passive"))
    )
    (net (code "122") (name "unconnected-(IC2-Pad35)") (class "Default")
      (node (ref "IC2") (pin "35") (pinfunction "35_35") (pintype "passive"))
    )
    (net (code "123") (name "unconnected-(IC2-Pad36)") (class "Default")
      (node (ref "IC2") (pin "36") (pinfunction "36_36") (pintype "passive"))
    )
    (net (code "124") (name "unconnected-(IC2-Pad37)") (class "Default")
      (node (ref "IC2") (pin "37") (pinfunction "37_37") (pintype "passive"))
    )
    (net (code "125") (name "unconnected-(IC2-Pad38)") (class "Default")
      (node (ref "IC2") (pin "38") (pinfunction "38_38") (pintype "passive"))
    )
    (net (code "126") (name "unconnected-(IC2-Pad39)") (class "Default")
      (node (ref "IC2") (pin "39") (pinfunction "39_39") (pintype "passive"))
    )
    (net (code "127") (name "unconnected-(IC2-Pad40)") (class "Default")
      (node (ref "IC2") (pin "40") (pinfunction "40_40") (pintype "passive"))
    )
    (net (code "128") (name "unconnected-(JP1-Pad1)") (class "Default")
      (node (ref "JP1") (pin "1") (pinfunction "1_1") (pintype "passive"))
    )
    (net (code "129") (name "unconnected-(JP1-Pad2)") (class "Default")
      (node (ref "JP1") (pin "2") (pinfunction "2_2") (pintype "passive"))
    )
    (net (code "130") (name "unconnected-(JP1-Pad3)") (class "Default")
      (node (ref "JP1") (pin "3") (pinfunction "3_3") (pintype "passive"))
    )
    (net (code "131") (name "unconnected-(JP1-Pad4)") (class "Default")
      (node (ref "JP1") (pin "4") (pinfunction "4_4") (pintype "passive"))
    )
    (net (code "132") (name "unconnected-(JP1-Pad5)") (class "Default")
      (node (ref "JP1") (pin "5") (pinfunction "5_5") (pintype "passive"))
    )
    (net (code "133") (name "unconnected-(JP1-Pad6)") (class "Default")
      (node (ref "JP1") (pin "6") (pinfunction "6_6") (pintype "passive"))
    )
    (net (code "134") (name "unconnected-(JP1-Pad7)") (class "Default")
      (node (ref "JP1") (pin "7") (pinfunction "7_7") (pintype "passive"))
    )
    (net (code "135") (name "unconnected-(JP1-Pad8)") (class "Default")
      (node (ref "JP1") (pin "8") (pinfunction "8_8") (pintype "passive"))
    )
    (net (code "136") (name "unconnected-(JP1-Pad9)") (class "Default")
      (node (ref "JP1") (pin "9") (pinfunction "9_9") (pintype "passive"))
    )
    (net (code "137") (name "unconnected-(JP1-Pad10)") (class "Default")
      (node (ref "JP1") (pin "10") (pinfunction "10_10") (pintype "passive"))
    )
    (net (code "138") (name "unconnected-(JP1-Pad11)") (class "Default")
      (node (ref "JP1") (pin "11") (pinfunction "11_11") (pintype "passive"))
    )
    (net (code "139") (name "unconnected-(JP1-Pad12)") (class "Default")
      (node (ref "JP1") (pin "12") (pinfunction "12_12") (pintype "passive"))
    )
    (net (code "140") (name "unconnected-(JP1-Pad13)") (class "Default")
      (node (ref "JP1") (pin "13") (pinfunction "13_13") (pintype "passive"))
    )
    (net (code "141") (name "unconnected-(JP1-Pad14)") (class "Default")
      (node (ref "JP1") (pin "14") (pinfunction "14_14") (pintype "passive"))
    )
    (net (code "142") (name "unconnected-(JP1-Pad15)") (class "Default")
      (node (ref "JP1") (pin "15") (pinfunction "15_15") (pintype "passive"))
    )
    (net (code "143") (name "unconnected-(JP1-Pad16)") (class "Default")
      (node (ref "JP1") (pin "16") (pinfunction "16_16") (pintype "passive"))
    )
    (net (code "144") (name "unconnected-(JP1-Pad17)") (class "Default")
      (node (ref "JP1") (pin "17") (pinfunction "17_17") (pintype "passive"))
    )
    (net (code "145") (name "unconnected-(JP1-Pad18)") (class "Default")
      (node (ref "JP1") (pin "18") (pinfunction "18_18") (pintype "passive"))
    )
    (net (code "146") (name "unconnected-(JP1-Pad19)") (class "Default")
      (node (ref "JP1") (pin "19") (pinfunction "19_19") (pintype "passive"))
    )
    (net (code "147") (name "unconnected-(JP1-Pad20)") (class "Default")
      (node (ref "JP1") (pin "20") (pinfunction "20_20") (pintype "passive"))
    )
    (net (code "148") (name "unconnected-(JP2-Pad1)") (class "Default")
      (node (ref "JP2") (pin "1") (pinfunction "1_1") (pintype "passive"))
    )
    (net (code "149") (name "unconnected-(JP2-Pad2)") (class "Default")
      (node (ref "JP2") (pin "2") (pinfunction "2_2") (pintype "passive"))
    )
    (net (code "150") (name "unconnected-(JP2-Pad3)") (class "Default")
      (node (ref "JP2") (pin "3") (pinfunction "3_3") (pintype "passive"))
    )
    (net (code "151") (name "unconnected-(JP2-Pad4)") (class "Default")
      (node (ref "JP2") (pin "4") (pinfunction "4_4") (pintype "passive"))
    )
    (net (code "152") (name "unconnected-(JP2-Pad5)") (class "Default")
      (node (ref "JP2") (pin "5") (pinfunction "5_5") (pintype "passive"))
    )
    (net (code "153") (name "unconnected-(JP2-Pad6)") (class "Default")
      (node (ref "JP2") (pin "6") (pinfunction "6_6") (pintype "passive"))
    )
    (net (code "154") (name "unconnected-(JP2-Pad7)") (class "Default")
      (node (ref "JP2") (pin "7") (pinfunction "7_7") (pintype "passive"))
    )
    (net (code "155") (name "unconnected-(JP2-Pad8)") (class "Default")
      (node (ref "JP2") (pin "8") (pinfunction "8_8") (pintype "passive"))
    )
    (net (code "156") (name "unconnected-(JP2-Pad9)") (class "Default")
      (node (ref "JP2") (pin "9") (pinfunction "9_9") (pintype "passive"))
    )
    (net (code "157") (name "unconnected-(JP2-Pad10)") (class "Default")
      (node (ref "JP2") (pin "10") (pinfunction "10_10") (pintype "passive"))
    )
    (net (code "158") (name "unconnected-(JP2-Pad11)") (class "Default")
      (node (ref "JP2") (pin "11") (pinfunction "11_11") (pintype "passive"))
    )
    (net (code "159") (name "unconnected-(JP2-Pad12)") (class "Default")
      (node (ref "JP2") (pin "12") (pinfunction "12_12") (pintype "passive"))
    )
    (net (code "160") (name "unconnected-(JP2-Pad13)") (class "Default")
      (node (ref "JP2") (pin "13") (pinfunction "13_13") (pintype "passive"))
    )
    (net (code "161") (name "unconnected-(JP2-Pad14)") (class "Default")
      (node (ref "JP2") (pin "14") (pinfunction "14_14") (pintype "passive"))
    )
    (net (code "162") (name "unconnected-(JP2-Pad15)") (class "Default")
      (node (ref "JP2") (pin "15") (pinfunction "15_15") (pintype "passive"))
    )
    (net (code "163") (name "unconnected-(JP2-Pad16)") (class "Default")
      (node (ref "JP2") (pin "16") (pinfunction "16_16") (pintype "passive"))
    )
    (net (code "164") (name "unconnected-(JP2-Pad17)") (class "Default")
      (node (ref "JP2") (pin "17") (pinfunction "17_17") (pintype "passive"))
    )
    (net (code "165") (name "unconnected-(JP2-Pad18)") (class "Default")
      (node (ref "JP2") (pin "18") (pinfunction "18_18") (pintype "passive"))
    )
    (net (code "166") (name "unconnected-(JP2-Pad19)") (class "Default")
      (node (ref "JP2") (pin "19") (pinfunction "19_19") (pintype "passive"))
    )
    (net (code "167") (name "unconnected-(JP2-Pad20)") (class "Default")
      (node (ref "JP2") (pin "20") (pinfunction "20_20") (pintype "passive"))
    )
    (net (code "168") (name "unconnected-(JP3-Pad1)") (class "Default")
      (node (ref "JP3") (pin "1") (pinfunction "1_1") (pintype "passive"))
    )
    (net (code "169") (name "unconnected-(JP3-Pad2)") (class "Default")
      (node (ref "JP3") (pin "2") (pinfunction "2_2") (pintype "passive"))
    )
    (net (code "170") (name "unconnected-(JP3-Pad3)") (class "Default")
      (node (ref "JP3") (pin "3") (pinfunction "3_3") (pintype "passive"))
    )
    (net (code "171") (name "unconnected-(JP3-Pad4)") (class "Default")
      (node (ref "JP3") (pin "4") (pinfunction "4_4") (pintype "passive"))
    )
    (net (code "172") (name "unconnected-(JP3-Pad5)") (class "Default")
      (node (ref "JP3") (pin "5") (pinfunction "5_5") (pintype "passive"))
    )
    (net (code "173") (name "unconnected-(JP3-Pad6)") (class "Default")
      (node (ref "JP3") (pin "6") (pinfunction "6_6") (pintype "passive"))
    )
    (net (code "174") (name "unconnected-(JP3-Pad7)") (class "Default")
      (node (ref "JP3") (pin "7") (pinfunction "7_7") (pintype "passive"))
    )
    (net (code "175") (name "unconnected-(JP3-Pad8)") (class "Default")
      (node (ref "JP3") (pin "8") (pinfunction "8_8") (pintype "passive"))
    )
    (net (code "176") (name "unconnected-(JP3-Pad9)") (class "Default")
      (node (ref "JP3") (pin "9") (pinfunction "9_9") (pintype "passive"))
    )
    (net (code "177") (name "unconnected-(JP3-Pad10)") (class "Default")
      (node (ref "JP3") (pin "10") (pinfunction "10_10") (pintype "passive"))
    )
    (net (code "178") (name "unconnected-(JP3-Pad11)") (class "Default")
      (node (ref "JP3") (pin "11") (pinfunction "11_11") (pintype "passive"))
    )
    (net (code "179") (name "unconnected-(JP3-Pad12)") (class "Default")
      (node (ref "JP3") (pin "12") (pinfunction "12_12") (pintype "passive"))
    )
    (net (code "180") (name "unconnected-(JP3-Pad13)") (class "Default")
      (node (ref "JP3") (pin "13") (pinfunction "13_13") (pintype "passive"))
    )
    (net (code "181") (name "unconnected-(JP3-Pad14)") (class "Default")
      (node (ref "JP3") (pin "14") (pinfunction "14_14") (pintype "passive"))
    )
    (net (code "182") (name "unconnected-(JP3-Pad15)") (class "Default")
      (node (ref "JP3") (pin "15") (pinfunction "15_15") (pintype "passive"))
    )
    (net (code "183") (name "unconnected-(JP3-Pad16)") (class "Default")
      (node (ref "JP3") (pin "16") (pinfunction "16_16") (pintype "passive"))
    )
    (net (code "184") (name "unconnected-(JP3-Pad17)") (class "Default")
      (node (ref "JP3") (pin "17") (pinfunction "17_17") (pintype "passive"))
    )
    (net (code "185") (name "unconnected-(JP3-Pad18)") (class "Default")
      (node (ref "JP3") (pin "18") (pinfunction "18_18") (pintype "passive"))
    )
    (net (code "186") (name "unconnected-(JP3-Pad19)") (class "Default")
      (node (ref "JP3") (pin "19") (pinfunction "19_19") (pintype "passive"))
    )
    (net (code "187") (name "unconnected-(JP3-Pad20)") (class "Default")
      (node (ref "JP3") (pin "20") (pinfunction "20_20") (pintype "passive"))
    )
  )
)
